# power.net
KiCad netlist of a schematic drawn in Altium Designer
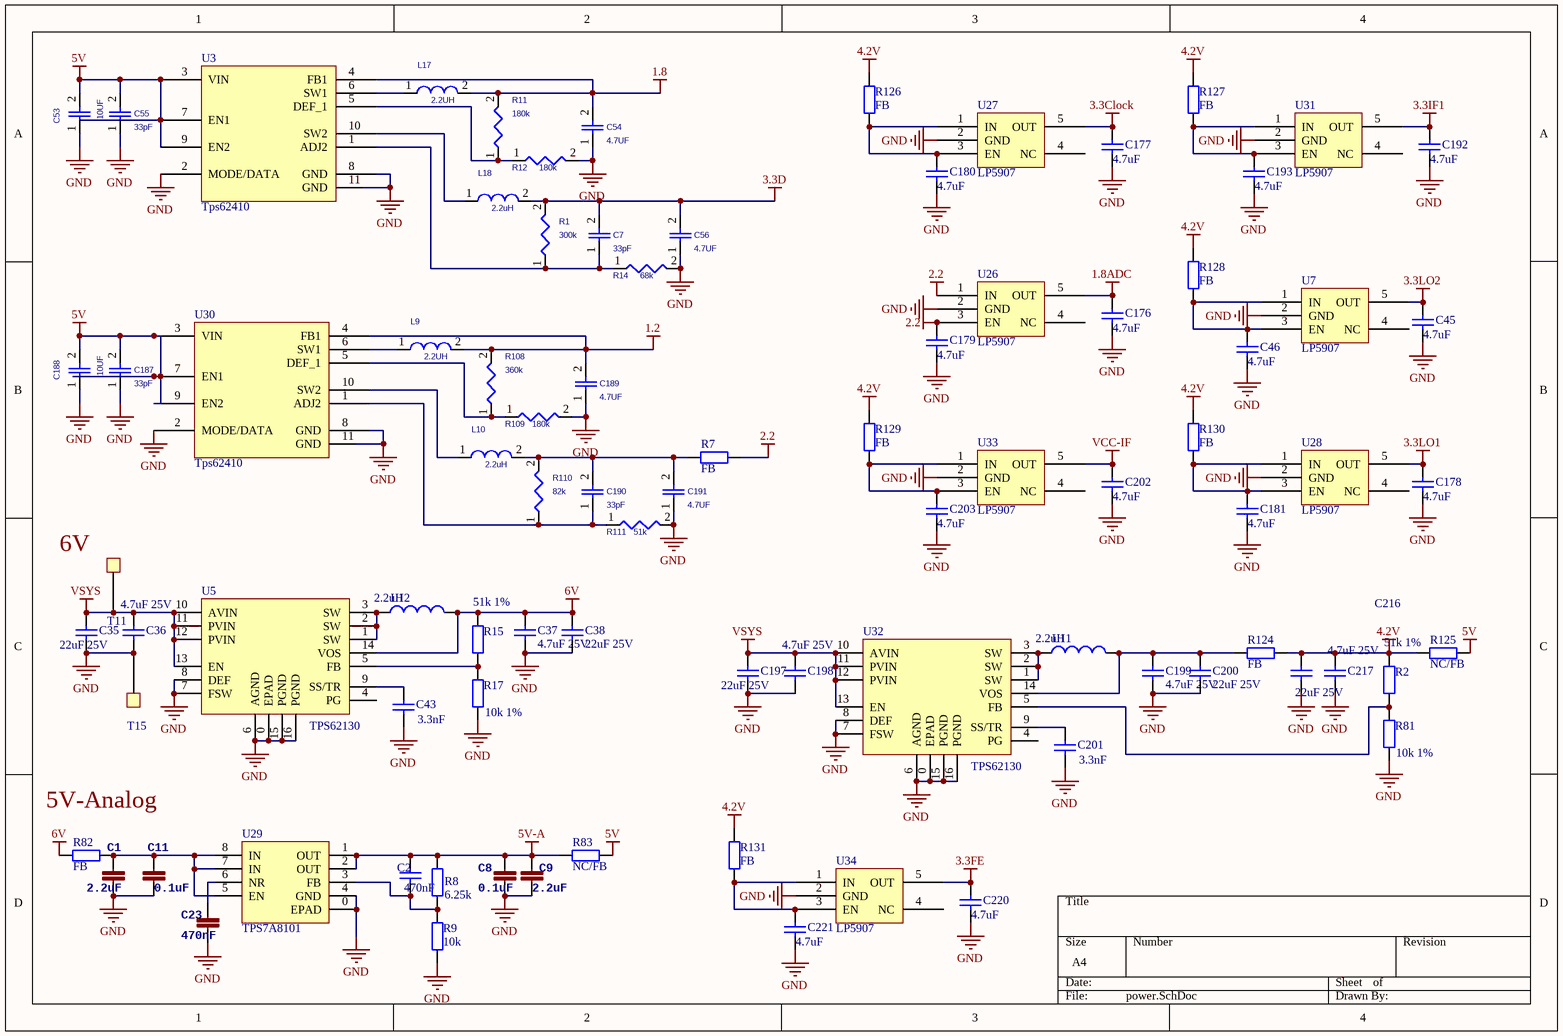
[diagram p0: power.SchDoc]

(export (version "E")
  (design (tool "Eeschema 10.0.6"))
  (components
    (comp (ref "C1")
      (value "2.2uF")
      (footprint "0603")
      (description "<b>Capacitor</b>\nStandard 0603 ceramic capacitor, and 0.1\" leaded capacitor.")
      (fields (field (name "PARTNO") "CC0402ZRY5V7BB104"))
      (libsource (lib "pixhawk2") (part "CAP0402-CAP"))
    )
    (comp (ref "C2")
      (value "470nF")
      (footprint "0402")
      (description "Capacitor")
      (fields (field (name "PUBLISHER") "Altium Limited"))
      (libsource (lib "RTC6705") (part "Cap"))
    )
    (comp (ref "C7") (value "33pF") (footprint "0402") (libsource (lib "*") (part "CAP/0402")))
    (comp (ref "C8")
      (value "0.1uF")
      (footprint "0603")
      (description "<b>Capacitor</b>\nStandard 0603 ceramic capacitor, and 0.1\" leaded capacitor.")
      (fields (field (name "PARTNO") "CC0402ZRY5V7BB104"))
      (libsource (lib "*") (part "CAP0402-CAP"))
    )
    (comp (ref "C9")
      (value "2.2uF")
      (footprint "0603")
      (description "<b>Capacitor</b>\nStandard 0603 ceramic capacitor, and 0.1\" leaded capacitor.")
      (fields (field (name "PARTNO") "CC0402ZRY5V7BB104"))
      (libsource (lib "pixhawk2") (part "CAP0402-CAP"))
    )
    (comp (ref "C11")
      (value "0.1uF")
      (footprint "0402")
      (description "<b>Capacitor</b>\nStandard 0603 ceramic capacitor, and 0.1\" leaded capacitor.")
      (fields (field (name "PARTNO") "CC0402ZRY5V7BB104"))
      (libsource (lib "*") (part "CAP0402-CAP"))
    )
    (comp (ref "C23")
      (value "470nF")
      (footprint "0402")
      (description "<b>Capacitor</b>\nStandard 0603 ceramic capacitor, and 0.1\" leaded capacitor.")
      (fields (field (name "PARTNO") "CC0402ZRY5V7BB104"))
      (libsource (lib "*") (part "CAP0402-CAP"))
    )
    (comp (ref "C35")
      (value "22uF 25V")
      (footprint "0805")
      (description "Capacitor")
      (fields (field (name "Comment") "Cap") (field (name "PUBLISHER") "Altium Limited"))
      (libsource (lib "RTC6705") (part "Cap"))
    )
    (comp (ref "C36")
      (value "4.7uF 25V")
      (footprint "0603")
      (description "Capacitor")
      (fields (field (name "Comment") "Cap") (field (name "PUBLISHER") "Altium Limited"))
      (libsource (lib "RTC6705") (part "Cap"))
    )
    (comp (ref "C37")
      (value "4.7uF 25V")
      (footprint "0603")
      (description "Capacitor")
      (fields (field (name "Comment") "Cap") (field (name "PUBLISHER") "Altium Limited"))
      (libsource (lib "RTC6705") (part "Cap"))
    )
    (comp (ref "C38")
      (value "22uF 25V")
      (footprint "0805")
      (description "Capacitor")
      (fields (field (name "Comment") "Cap") (field (name "PUBLISHER") "Altium Limited"))
      (libsource (lib "RTC6705") (part "Cap"))
    )
    (comp (ref "C43")
      (value "3.3nF")
      (footprint "0402")
      (description "Capacitor")
      (fields (field (name "PUBLISHER") "Altium Limited"))
      (libsource (lib "RTC6705") (part "Cap"))
    )
    (comp (ref "C45")
      (value "4.7uF")
      (footprint "0603")
      (description "Capacitor")
      (fields (field (name "PUBLISHER") "Altium Limited"))
      (libsource (lib "RTC6705") (part "Cap"))
    )
    (comp (ref "C46")
      (value "4.7uF")
      (footprint "0603")
      (description "Capacitor")
      (fields (field (name "PUBLISHER") "Altium Limited"))
      (libsource (lib "RTC6705") (part "Cap"))
    )
    (comp (ref "C53") (value "10UF") (footprint "0805") (libsource (lib "*") (part "CAP/0402")))
    (comp (ref "C54") (value "4.7UF") (footprint "0805") (libsource (lib "*") (part "CAP/0402")))
    (comp (ref "C55") (value "33pF") (footprint "0603") (libsource (lib "*") (part "CAP/0402")))
    (comp (ref "C56") (value "4.7UF") (footprint "0805") (libsource (lib "*") (part "CAP/0402")))
    (comp (ref "C176")
      (value "4.7uF")
      (footprint "0603")
      (description "Capacitor")
      (fields (field (name "PUBLISHER") "Altium Limited"))
      (libsource (lib "RTC6705") (part "Cap"))
    )
    (comp (ref "C177")
      (value "4.7uF")
      (footprint "0603")
      (description "Capacitor")
      (fields (field (name "PUBLISHER") "Altium Limited"))
      (libsource (lib "RTC6705") (part "Cap"))
    )
    (comp (ref "C178")
      (value "4.7uF")
      (footprint "0603")
      (description "Capacitor")
      (fields (field (name "PUBLISHER") "Altium Limited"))
      (libsource (lib "RTC6705") (part "Cap"))
    )
    (comp (ref "C179")
      (value "4.7uF")
      (footprint "0603")
      (description "Capacitor")
      (fields (field (name "PUBLISHER") "Altium Limited"))
      (libsource (lib "RTC6705") (part "Cap"))
    )
    (comp (ref "C180")
      (value "4.7uF")
      (footprint "0603")
      (description "Capacitor")
      (fields (field (name "PUBLISHER") "Altium Limited"))
      (libsource (lib "RTC6705") (part "Cap"))
    )
    (comp (ref "C181")
      (value "4.7uF")
      (footprint "0603")
      (description "Capacitor")
      (fields (field (name "PUBLISHER") "Altium Limited"))
      (libsource (lib "RTC6705") (part "Cap"))
    )
    (comp (ref "C187") (value "33pF") (footprint "0603") (libsource (lib "*") (part "CAP/0402")))
    (comp (ref "C188") (value "10UF") (footprint "0805") (libsource (lib "*") (part "CAP/0402")))
    (comp (ref "C189") (value "4.7UF") (footprint "0805") (libsource (lib "*") (part "CAP/0402")))
    (comp (ref "C190") (value "33pF") (footprint "0402") (libsource (lib "*") (part "CAP/0402")))
    (comp (ref "C191") (value "4.7UF") (footprint "0805") (libsource (lib "*") (part "CAP/0402")))
    (comp (ref "C192")
      (value "4.7uF")
      (footprint "0603")
      (description "Capacitor")
      (fields (field (name "PUBLISHER") "Altium Limited"))
      (libsource (lib "RTC6705") (part "Cap"))
    )
    (comp (ref "C193")
      (value "4.7uF")
      (footprint "0603")
      (description "Capacitor")
      (fields (field (name "PUBLISHER") "Altium Limited"))
      (libsource (lib "RTC6705") (part "Cap"))
    )
    (comp (ref "C197")
      (value "22uF 25V")
      (footprint "0805")
      (description "Capacitor")
      (fields (field (name "Comment") "Cap") (field (name "PUBLISHER") "Altium Limited"))
      (libsource (lib "RTC6705") (part "Cap"))
    )
    (comp (ref "C198")
      (value "4.7uF 25V")
      (footprint "0603")
      (description "Capacitor")
      (fields (field (name "Comment") "Cap") (field (name "PUBLISHER") "Altium Limited"))
      (libsource (lib "RTC6705") (part "Cap"))
    )
    (comp (ref "C199")
      (value "4.7uF 25V")
      (footprint "0603")
      (description "Capacitor")
      (fields (field (name "Comment") "Cap") (field (name "PUBLISHER") "Altium Limited"))
      (libsource (lib "RTC6705") (part "Cap"))
    )
    (comp (ref "C200")
      (value "22uF 25V")
      (footprint "0805")
      (description "Capacitor")
      (fields (field (name "Comment") "Cap") (field (name "PUBLISHER") "Altium Limited"))
      (libsource (lib "RTC6705") (part "Cap"))
    )
    (comp (ref "C201")
      (value "3.3nF")
      (footprint "0402")
      (description "Capacitor")
      (fields (field (name "PUBLISHER") "Altium Limited"))
      (libsource (lib "RTC6705") (part "Cap"))
    )
    (comp (ref "C202")
      (value "4.7uF")
      (footprint "0603")
      (description "Capacitor")
      (fields (field (name "PUBLISHER") "Altium Limited"))
      (libsource (lib "RTC6705") (part "Cap"))
    )
    (comp (ref "C203")
      (value "4.7uF")
      (footprint "0603")
      (description "Capacitor")
      (fields (field (name "PUBLISHER") "Altium Limited"))
      (libsource (lib "RTC6705") (part "Cap"))
    )
    (comp (ref "C216")
      (value "4.7uF 25V")
      (footprint "0603")
      (description "Capacitor")
      (fields (field (name "Comment") "Cap") (field (name "PUBLISHER") "Altium Limited"))
      (libsource (lib "RTC6705") (part "Cap"))
    )
    (comp (ref "C217")
      (value "22uF 25V")
      (footprint "0805")
      (description "Capacitor")
      (fields (field (name "Comment") "Cap") (field (name "PUBLISHER") "Altium Limited"))
      (libsource (lib "RTC6705") (part "Cap"))
    )
    (comp (ref "C220")
      (value "4.7uF")
      (footprint "0603")
      (description "Capacitor")
      (fields (field (name "PUBLISHER") "Altium Limited"))
      (libsource (lib "RTC6705") (part "Cap"))
    )
    (comp (ref "C221")
      (value "4.7uF")
      (footprint "0603")
      (description "Capacitor")
      (fields (field (name "PUBLISHER") "Altium Limited"))
      (libsource (lib "RTC6705") (part "Cap"))
    )
    (comp (ref "L9") (value "2.2UH") (footprint "0806") (libsource (lib "*") (part "L/2.5*2.0")))
    (comp (ref "L10") (value "2.2uH") (footprint "0806") (libsource (lib "*") (part "L/2.5*2.0")))
    (comp (ref "L11")
      (value "2.2uH")
      (footprint "L4015")
      (description "Inductor")
      (fields (field (name "PUBLISHER") "Altium Limited"))
      (libsource (lib "Miscellaneous Devices") (part "Inductor"))
    )
    (comp (ref "L12")
      (value "2.2uH")
      (footprint "L4015")
      (description "Inductor")
      (fields (field (name "PUBLISHER") "Altium Limited"))
      (libsource (lib "Miscellaneous Devices") (part "Inductor"))
    )
    (comp (ref "L17") (value "2.2UH") (footprint "0806") (libsource (lib "*") (part "L/2.5*2.0")))
    (comp (ref "L18") (value "2.2uH") (footprint "0806") (libsource (lib "*") (part "L/2.5*2.0")))
    (comp (ref "R1") (value "300k") (footprint "0402") (libsource (lib "*") (part "RES/0402_3")))
    (comp (ref "R2")
      (value "51k 1%")
      (footprint "0402")
      (description "Resistor")
      (fields (field (name "PUBLISHER") "Altium Limited"))
      (libsource (lib "RTC6705") (part "Res2"))
    )
    (comp (ref "R7")
      (value "FB")
      (footprint "0603")
      (description "Resistor")
      (fields (field (name "PUBLISHER") "Altium Limited"))
      (libsource (lib "") (part "Res2_1"))
    )
    (comp (ref "R8")
      (value "6.25k")
      (footprint "0402")
      (description "Resistor")
      (fields (field (name "PUBLISHER") "Altium Limited"))
      (libsource (lib "Miscellaneous Devices") (part "Res2"))
    )
    (comp (ref "R9")
      (value "10k")
      (footprint "0402")
      (description "Resistor")
      (fields (field (name "PUBLISHER") "Altium Limited"))
      (libsource (lib "Miscellaneous Devices") (part "Res2"))
    )
    (comp (ref "R11") (value "180k") (footprint "0402") (libsource (lib "*") (part "RES/0402_3")))
    (comp (ref "R12") (value "180k") (footprint "0402") (libsource (lib "*") (part "RES/0402_3")))
    (comp (ref "R14") (value "68k") (footprint "0402") (libsource (lib "*") (part "RES/0402_3")))
    (comp (ref "R15")
      (value "51k 1%")
      (footprint "0402")
      (description "Resistor")
      (fields (field (name "PUBLISHER") "Altium Limited"))
      (libsource (lib "RTC6705") (part "Res2"))
    )
    (comp (ref "R17")
      (value "10k 1%")
      (footprint "0402")
      (description "Resistor")
      (fields (field (name "PUBLISHER") "Altium Limited"))
      (libsource (lib "RTC6705") (part "Res2"))
    )
    (comp (ref "R81")
      (value "10k 1%")
      (footprint "0402")
      (description "Resistor")
      (fields (field (name "PUBLISHER") "Altium Limited"))
      (libsource (lib "RTC6705") (part "Res2"))
    )
    (comp (ref "R82")
      (value "FB")
      (footprint "0603")
      (description "Resistor")
      (fields (field (name "PUBLISHER") "Altium Limited"))
      (libsource (lib "") (part "Res2_1"))
    )
    (comp (ref "R83")
      (value "NC/FB")
      (footprint "0603")
      (description "Resistor")
      (fields (field (name "PUBLISHER") "Altium Limited"))
      (libsource (lib "") (part "Res2_1"))
    )
    (comp (ref "R108") (value "360k") (footprint "0402") (libsource (lib "*") (part "RES/0402_3")))
    (comp (ref "R109") (value "180k") (footprint "0402") (libsource (lib "*") (part "RES/0402_3")))
    (comp (ref "R110") (value "82k") (footprint "0402") (libsource (lib "*") (part "RES/0402_3")))
    (comp (ref "R111") (value "51k") (footprint "0402") (libsource (lib "*") (part "RES/0402_3")))
    (comp (ref "R124")
      (value "FB")
      (footprint "0603")
      (description "Resistor")
      (fields (field (name "PUBLISHER") "Altium Limited"))
      (libsource (lib "") (part "Res2_1"))
    )
    (comp (ref "R125")
      (value "NC/FB")
      (footprint "0603")
      (description "Resistor")
      (fields (field (name "PUBLISHER") "Altium Limited"))
      (libsource (lib "") (part "Res2_1"))
    )
    (comp (ref "R126")
      (value "FB")
      (footprint "0603")
      (description "Resistor")
      (fields (field (name "PUBLISHER") "Altium Limited"))
      (libsource (lib "Miscellaneous Devices") (part "Res2"))
    )
    (comp (ref "R127")
      (value "FB")
      (footprint "0603")
      (description "Resistor")
      (fields (field (name "PUBLISHER") "Altium Limited"))
      (libsource (lib "Miscellaneous Devices") (part "Res2"))
    )
    (comp (ref "R128")
      (value "FB")
      (footprint "0603")
      (description "Resistor")
      (fields (field (name "PUBLISHER") "Altium Limited"))
      (libsource (lib "Miscellaneous Devices") (part "Res2"))
    )
    (comp (ref "R129")
      (value "FB")
      (footprint "0603")
      (description "Resistor")
      (fields (field (name "PUBLISHER") "Altium Limited"))
      (libsource (lib "Miscellaneous Devices") (part "Res2"))
    )
    (comp (ref "R130")
      (value "FB")
      (footprint "0603")
      (description "Resistor")
      (fields (field (name "PUBLISHER") "Altium Limited"))
      (libsource (lib "Miscellaneous Devices") (part "Res2"))
    )
    (comp (ref "R131")
      (value "FB")
      (footprint "0603")
      (description "Resistor")
      (fields (field (name "PUBLISHER") "Altium Limited"))
      (libsource (lib "Miscellaneous Devices") (part "Res2"))
    )
    (comp (ref "T11") (value "TestPad") (footprint "TestPad") (libsource (lib "sch") (part "TestPad")))
    (comp (ref "T15") (value "TestPad") (footprint "TestPad") (libsource (lib "") (part "TestPad_1")))
    (comp (ref "U3") (value "Tps62410") (footprint "DFN-10P-3X3") (libsource (lib "Euler") (part "Tps62410")))
    (comp (ref "U5") (value "TPS62130") (footprint "TPS62130") (libsource (lib "sch") (part "TPS62130")))
    (comp (ref "U7") (value "LP5907") (footprint "SOT23-5") (libsource (lib "RTC6705") (part "LP5907")))
    (comp (ref "U26") (value "LP5907") (footprint "SOT23-5") (libsource (lib "RTC6705") (part "LP5907")))
    (comp (ref "U27") (value "LP5907") (footprint "SOT23-5") (libsource (lib "RTC6705") (part "LP5907")))
    (comp (ref "U28") (value "LP5907") (footprint "SOT23-5") (libsource (lib "RTC6705") (part "LP5907")))
    (comp (ref "U29")
      (value "TPS7A8101")
      (footprint "TPS7A8101")
      (libsource (lib "F4SDR") (part "TPS7A8101"))
    )
    (comp (ref "U30")
      (value "Tps62410")
      (footprint "DFN-10P-3X3")
      (libsource (lib "Euler") (part "Tps62410"))
    )
    (comp (ref "U31") (value "LP5907") (footprint "SOT23-5") (libsource (lib "RTC6705") (part "LP5907")))
    (comp (ref "U32") (value "TPS62130") (footprint "TPS62130") (libsource (lib "sch") (part "TPS62130")))
    (comp (ref "U33") (value "LP5907") (footprint "SOT23-5") (libsource (lib "RTC6705") (part "LP5907")))
    (comp (ref "U34") (value "LP5907") (footprint "SOT23-5") (libsource (lib "RTC6705") (part "LP5907")))
  )
  (nets
    (net (code "1") (name "1.2") (class "Default")
      (node (ref "C189") (pin "2") (pinfunction "2_2") (pintype "passive"))
      (node (ref "L9") (pin "2") (pinfunction "2_2") (pintype "passive"))
      (node (ref "R108") (pin "2") (pinfunction "2_2") (pintype "passive"))
      (node (ref "U30") (pin "4") (pinfunction "FB1_4") (pintype "passive"))
    )
    (net (code "2") (name "1.8") (class "Default")
      (node (ref "C54") (pin "2") (pinfunction "2_2") (pintype "passive"))
      (node (ref "L17") (pin "2") (pinfunction "2_2") (pintype "passive"))
      (node (ref "R11") (pin "2") (pinfunction "2_2") (pintype "passive"))
      (node (ref "U3") (pin "4") (pinfunction "FB1_4") (pintype "passive"))
    )
    (net (code "3") (name "1.8ADC") (class "Default")
      (node (ref "C176") (pin "2") (pinfunction "2_2") (pintype "passive"))
      (node (ref "U26") (pin "5") (pinfunction "OUT_5") (pintype "passive"))
    )
    (net (code "4") (name "2.2") (class "Default")
      (node (ref "C179") (pin "2") (pinfunction "2_2") (pintype "passive"))
      (node (ref "R7") (pin "1") (pinfunction "1_1") (pintype "passive"))
      (node (ref "U26") (pin "1") (pinfunction "IN_1") (pintype "passive"))
      (node (ref "U26") (pin "3") (pinfunction "EN_3") (pintype "passive"))
    )
    (net (code "5") (name "3.3Clock") (class "Default")
      (node (ref "C177") (pin "2") (pinfunction "2_2") (pintype "passive"))
      (node (ref "U27") (pin "5") (pinfunction "OUT_5") (pintype "passive"))
    )
    (net (code "6") (name "3.3D") (class "Default")
      (node (ref "C56") (pin "2") (pinfunction "2_2") (pintype "passive"))
      (node (ref "C7") (pin "2") (pinfunction "2_2") (pintype "passive"))
      (node (ref "L18") (pin "2") (pinfunction "2_2") (pintype "passive"))
      (node (ref "R1") (pin "2") (pinfunction "2_2") (pintype "passive"))
    )
    (net (code "7") (name "3.3FE") (class "Default")
      (node (ref "C220") (pin "2") (pinfunction "2_2") (pintype "passive"))
      (node (ref "U34") (pin "5") (pinfunction "OUT_5") (pintype "passive"))
    )
    (net (code "8") (name "3.3IF1") (class "Default")
      (node (ref "C192") (pin "2") (pinfunction "2_2") (pintype "passive"))
      (node (ref "U31") (pin "5") (pinfunction "OUT_5") (pintype "passive"))
    )
    (net (code "9") (name "3.3LO1") (class "Default")
      (node (ref "C178") (pin "2") (pinfunction "2_2") (pintype "passive"))
      (node (ref "U28") (pin "5") (pinfunction "OUT_5") (pintype "passive"))
    )
    (net (code "10") (name "3.3LO2") (class "Default")
      (node (ref "C45") (pin "2") (pinfunction "2_2") (pintype "passive"))
      (node (ref "U7") (pin "5") (pinfunction "OUT_5") (pintype "passive"))
    )
    (net (code "11") (name "4.2V") (class "Default")
      (node (ref "C216") (pin "2") (pinfunction "2_2") (pintype "passive"))
      (node (ref "C217") (pin "2") (pinfunction "2_2") (pintype "passive"))
      (node (ref "R124") (pin "1") (pinfunction "1_1") (pintype "passive"))
      (node (ref "R125") (pin "2") (pinfunction "2_2") (pintype "passive"))
      (node (ref "R126") (pin "1") (pinfunction "1_1") (pintype "passive"))
      (node (ref "R127") (pin "1") (pinfunction "1_1") (pintype "passive"))
      (node (ref "R128") (pin "1") (pinfunction "1_1") (pintype "passive"))
      (node (ref "R129") (pin "1") (pinfunction "1_1") (pintype "passive"))
      (node (ref "R130") (pin "1") (pinfunction "1_1") (pintype "passive"))
      (node (ref "R131") (pin "1") (pinfunction "1_1") (pintype "passive"))
      (node (ref "R2") (pin "1") (pinfunction "1_1") (pintype "passive"))
    )
    (net (code "12") (name "5V") (class "Default")
      (node (ref "C187") (pin "2") (pinfunction "2_2") (pintype "passive"))
      (node (ref "C188") (pin "2") (pinfunction "2_2") (pintype "passive"))
      (node (ref "C53") (pin "2") (pinfunction "2_2") (pintype "passive"))
      (node (ref "C55") (pin "2") (pinfunction "2_2") (pintype "passive"))
      (node (ref "R125") (pin "1") (pinfunction "1_1") (pintype "passive"))
      (node (ref "R83") (pin "1") (pinfunction "1_1") (pintype "passive"))
      (node (ref "U3") (pin "3") (pinfunction "VIN_3") (pintype "passive"))
      (node (ref "U3") (pin "7") (pinfunction "EN1_7") (pintype "passive"))
      (node (ref "U3") (pin "9") (pinfunction "EN2_9") (pintype "passive"))
      (node (ref "U30") (pin "3") (pinfunction "VIN_3") (pintype "passive"))
      (node (ref "U30") (pin "7") (pinfunction "EN1_7") (pintype "passive"))
      (node (ref "U30") (pin "9") (pinfunction "EN2_9") (pintype "passive"))
    )
    (net (code "13") (name "5V-A") (class "Default")
      (node (ref "C2") (pin "1") (pinfunction "1_1") (pintype "passive"))
      (node (ref "C8") (pin "2") (pinfunction "2_2") (pintype "passive"))
      (node (ref "C9") (pin "2") (pinfunction "2_2") (pintype "passive"))
      (node (ref "R8") (pin "1") (pinfunction "1_1") (pintype "passive"))
      (node (ref "R83") (pin "2") (pinfunction "2_2") (pintype "passive"))
      (node (ref "U29") (pin "1") (pinfunction "OUT_1") (pintype "passive"))
      (node (ref "U29") (pin "2") (pinfunction "OUT_2") (pintype "passive"))
    )
    (net (code "14") (name "6V") (class "Default")
      (node (ref "C37") (pin "2") (pinfunction "2_2") (pintype "passive"))
      (node (ref "C38") (pin "2") (pinfunction "2_2") (pintype "passive"))
      (node (ref "L12") (pin "2") (pinfunction "2_2") (pintype "passive"))
      (node (ref "R15") (pin "1") (pinfunction "1_1") (pintype "passive"))
      (node (ref "R82") (pin "2") (pinfunction "2_2") (pintype "passive"))
      (node (ref "U5") (pin "14") (pinfunction "VOS_14") (pintype "passive"))
    )
    (net (code "15") (name "GND") (class "Default")
      (node (ref "C1") (pin "1") (pinfunction "1_1") (pintype "passive"))
      (node (ref "C11") (pin "1") (pinfunction "1_1") (pintype "passive"))
      (node (ref "C176") (pin "1") (pinfunction "1_1") (pintype "passive"))
      (node (ref "C177") (pin "1") (pinfunction "1_1") (pintype "passive"))
      (node (ref "C178") (pin "1") (pinfunction "1_1") (pintype "passive"))
      (node (ref "C179") (pin "1") (pinfunction "1_1") (pintype "passive"))
      (node (ref "C180") (pin "1") (pinfunction "1_1") (pintype "passive"))
      (node (ref "C181") (pin "1") (pinfunction "1_1") (pintype "passive"))
      (node (ref "C187") (pin "1") (pinfunction "1_1") (pintype "passive"))
      (node (ref "C188") (pin "1") (pinfunction "1_1") (pintype "passive"))
      (node (ref "C189") (pin "1") (pinfunction "1_1") (pintype "passive"))
      (node (ref "C191") (pin "1") (pinfunction "1_1") (pintype "passive"))
      (node (ref "C192") (pin "1") (pinfunction "1_1") (pintype "passive"))
      (node (ref "C193") (pin "1") (pinfunction "1_1") (pintype "passive"))
      (node (ref "C197") (pin "2") (pinfunction "2_2") (pintype "passive"))
      (node (ref "C198") (pin "2") (pinfunction "2_2") (pintype "passive"))
      (node (ref "C199") (pin "1") (pinfunction "1_1") (pintype "passive"))
      (node (ref "C200") (pin "1") (pinfunction "1_1") (pintype "passive"))
      (node (ref "C201") (pin "2") (pinfunction "2_2") (pintype "passive"))
      (node (ref "C202") (pin "1") (pinfunction "1_1") (pintype "passive"))
      (node (ref "C203") (pin "1") (pinfunction "1_1") (pintype "passive"))
      (node (ref "C216") (pin "1") (pinfunction "1_1") (pintype "passive"))
      (node (ref "C217") (pin "1") (pinfunction "1_1") (pintype "passive"))
      (node (ref "C220") (pin "1") (pinfunction "1_1") (pintype "passive"))
      (node (ref "C221") (pin "1") (pinfunction "1_1") (pintype "passive"))
      (node (ref "C23") (pin "1") (pinfunction "1_1") (pintype "passive"))
      (node (ref "C35") (pin "2") (pinfunction "2_2") (pintype "passive"))
      (node (ref "C36") (pin "2") (pinfunction "2_2") (pintype "passive"))
      (node (ref "C37") (pin "1") (pinfunction "1_1") (pintype "passive"))
      (node (ref "C38") (pin "1") (pinfunction "1_1") (pintype "passive"))
      (node (ref "C43") (pin "2") (pinfunction "2_2") (pintype "passive"))
      (node (ref "C45") (pin "1") (pinfunction "1_1") (pintype "passive"))
      (node (ref "C46") (pin "1") (pinfunction "1_1") (pintype "passive"))
      (node (ref "C53") (pin "1") (pinfunction "1_1") (pintype "passive"))
      (node (ref "C54") (pin "1") (pinfunction "1_1") (pintype "passive"))
      (node (ref "C55") (pin "1") (pinfunction "1_1") (pintype "passive"))
      (node (ref "C56") (pin "1") (pinfunction "1_1") (pintype "passive"))
      (node (ref "C8") (pin "1") (pinfunction "1_1") (pintype "passive"))
      (node (ref "C9") (pin "1") (pinfunction "1_1") (pintype "passive"))
      (node (ref "R109") (pin "2") (pinfunction "2_2") (pintype "passive"))
      (node (ref "R111") (pin "2") (pinfunction "2_2") (pintype "passive"))
      (node (ref "R12") (pin "2") (pinfunction "2_2") (pintype "passive"))
      (node (ref "R14") (pin "2") (pinfunction "2_2") (pintype "passive"))
      (node (ref "R17") (pin "2") (pinfunction "2_2") (pintype "passive"))
      (node (ref "R81") (pin "2") (pinfunction "2_2") (pintype "passive"))
      (node (ref "R9") (pin "2") (pinfunction "2_2") (pintype "passive"))
      (node (ref "T15") (pin "1") (pinfunction "3_1") (pintype "passive"))
      (node (ref "U26") (pin "2") (pinfunction "GND_2") (pintype "passive"))
      (node (ref "U27") (pin "2") (pinfunction "GND_2") (pintype "passive"))
      (node (ref "U28") (pin "2") (pinfunction "GND_2") (pintype "passive"))
      (node (ref "U29") (pin "0") (pinfunction "EPAD_0") (pintype "passive"))
      (node (ref "U29") (pin "4") (pinfunction "GND_4") (pintype "passive"))
      (node (ref "U3") (pin "11") (pinfunction "GND_11") (pintype "passive"))
      (node (ref "U3") (pin "2") (pinfunction "MODE/DATA_2") (pintype "passive"))
      (node (ref "U3") (pin "8") (pinfunction "GND_8") (pintype "passive"))
      (node (ref "U30") (pin "11") (pinfunction "GND_11") (pintype "passive"))
      (node (ref "U30") (pin "2") (pinfunction "MODE/DATA_2") (pintype "passive"))
      (node (ref "U30") (pin "8") (pinfunction "GND_8") (pintype "passive"))
      (node (ref "U31") (pin "2") (pinfunction "GND_2") (pintype "passive"))
      (node (ref "U32") (pin "0") (pinfunction "EPAD_0") (pintype "passive"))
      (node (ref "U32") (pin "15") (pinfunction "PGND_15") (pintype "passive"))
      (node (ref "U32") (pin "16") (pinfunction "PGND_16") (pintype "passive"))
      (node (ref "U32") (pin "6") (pinfunction "AGND_6") (pintype "passive"))
      (node (ref "U32") (pin "7") (pinfunction "FSW_7") (pintype "passive"))
      (node (ref "U32") (pin "8") (pinfunction "DEF_8") (pintype "passive"))
      (node (ref "U33") (pin "2") (pinfunction "GND_2") (pintype "passive"))
      (node (ref "U34") (pin "2") (pinfunction "GND_2") (pintype "passive"))
      (node (ref "U5") (pin "0") (pinfunction "EPAD_0") (pintype "passive"))
      (node (ref "U5") (pin "15") (pinfunction "PGND_15") (pintype "passive"))
      (node (ref "U5") (pin "16") (pinfunction "PGND_16") (pintype "passive"))
      (node (ref "U5") (pin "6") (pinfunction "AGND_6") (pintype "passive"))
      (node (ref "U5") (pin "7") (pinfunction "FSW_7") (pintype "passive"))
      (node (ref "U5") (pin "8") (pinfunction "DEF_8") (pintype "passive"))
      (node (ref "U7") (pin "2") (pinfunction "GND_2") (pintype "passive"))
    )
    (net (code "16") (name "Net-(C190-Pad2)") (class "Default")
      (node (ref "C190") (pin "2") (pinfunction "2_2") (pintype "passive"))
      (node (ref "C191") (pin "2") (pinfunction "2_2") (pintype "passive"))
      (node (ref "L10") (pin "2") (pinfunction "2_2") (pintype "passive"))
      (node (ref "R110") (pin "2") (pinfunction "2_2") (pintype "passive"))
      (node (ref "R7") (pin "2") (pinfunction "2_2") (pintype "passive"))
    )
    (net (code "17") (name "Net-(L11-Pad1)") (class "Default")
      (node (ref "L11") (pin "1") (pinfunction "1_1") (pintype "passive"))
      (node (ref "U32") (pin "1") (pinfunction "SW_1") (pintype "passive"))
      (node (ref "U32") (pin "2") (pinfunction "SW_2") (pintype "passive"))
      (node (ref "U32") (pin "3") (pinfunction "SW_3") (pintype "passive"))
    )
    (net (code "18") (name "Net-(L12-Pad1)") (class "Default")
      (node (ref "L12") (pin "1") (pinfunction "1_1") (pintype "passive"))
      (node (ref "U5") (pin "1") (pinfunction "SW_1") (pintype "passive"))
      (node (ref "U5") (pin "2") (pinfunction "SW_2") (pintype "passive"))
      (node (ref "U5") (pin "3") (pinfunction "SW_3") (pintype "passive"))
    )
    (net (code "19") (name "Net-(U3-ADJ2)") (class "Default")
      (node (ref "C7") (pin "1") (pinfunction "1_1") (pintype "passive"))
      (node (ref "R1") (pin "1") (pinfunction "1_1") (pintype "passive"))
      (node (ref "R14") (pin "1") (pinfunction "1_1") (pintype "passive"))
      (node (ref "U3") (pin "1") (pinfunction "ADJ2_1") (pintype "passive"))
    )
    (net (code "20") (name "Net-(U3-DEF_1)") (class "Default")
      (node (ref "R11") (pin "1") (pinfunction "1_1") (pintype "passive"))
      (node (ref "R12") (pin "1") (pinfunction "1_1") (pintype "passive"))
      (node (ref "U3") (pin "5") (pinfunction "DEF_1_5") (pintype "passive"))
    )
    (net (code "21") (name "Net-(U3-SW1)") (class "Default")
      (node (ref "L17") (pin "1") (pinfunction "1_1") (pintype "passive"))
      (node (ref "U3") (pin "6") (pinfunction "SW1_6") (pintype "passive"))
    )
    (net (code "22") (name "Net-(U3-SW2)") (class "Default")
      (node (ref "L18") (pin "1") (pinfunction "1_1") (pintype "passive"))
      (node (ref "U3") (pin "10") (pinfunction "SW2_10") (pintype "passive"))
    )
    (net (code "23") (name "Net-(U5-FB)") (class "Default")
      (node (ref "R15") (pin "2") (pinfunction "2_2") (pintype "passive"))
      (node (ref "R17") (pin "1") (pinfunction "1_1") (pintype "passive"))
      (node (ref "U5") (pin "5") (pinfunction "FB_5") (pintype "passive"))
    )
    (net (code "24") (name "Net-(U5-SS{slash}TR)") (class "Default")
      (node (ref "C43") (pin "1") (pinfunction "1_1") (pintype "passive"))
      (node (ref "U5") (pin "9") (pinfunction "SS/TR_9") (pintype "passive"))
    )
    (net (code "25") (name "Net-(U7-EN)") (class "Default")
      (node (ref "C46") (pin "2") (pinfunction "2_2") (pintype "passive"))
      (node (ref "R128") (pin "2") (pinfunction "2_2") (pintype "passive"))
      (node (ref "U7") (pin "1") (pinfunction "IN_1") (pintype "passive"))
      (node (ref "U7") (pin "3") (pinfunction "EN_3") (pintype "passive"))
    )
    (net (code "26") (name "Net-(U27-EN)") (class "Default")
      (node (ref "C180") (pin "2") (pinfunction "2_2") (pintype "passive"))
      (node (ref "R126") (pin "2") (pinfunction "2_2") (pintype "passive"))
      (node (ref "U27") (pin "1") (pinfunction "IN_1") (pintype "passive"))
      (node (ref "U27") (pin "3") (pinfunction "EN_3") (pintype "passive"))
    )
    (net (code "27") (name "Net-(U28-EN)") (class "Default")
      (node (ref "C181") (pin "2") (pinfunction "2_2") (pintype "passive"))
      (node (ref "R130") (pin "2") (pinfunction "2_2") (pintype "passive"))
      (node (ref "U28") (pin "1") (pinfunction "IN_1") (pintype "passive"))
      (node (ref "U28") (pin "3") (pinfunction "EN_3") (pintype "passive"))
    )
    (net (code "28") (name "Net-(U29-EN)") (class "Default")
      (node (ref "C1") (pin "2") (pinfunction "2_2") (pintype "passive"))
      (node (ref "C11") (pin "2") (pinfunction "2_2") (pintype "passive"))
      (node (ref "R82") (pin "1") (pinfunction "1_1") (pintype "passive"))
      (node (ref "U29") (pin "5") (pinfunction "EN_5") (pintype "passive"))
      (node (ref "U29") (pin "7") (pinfunction "IN_7") (pintype "passive"))
      (node (ref "U29") (pin "8") (pinfunction "IN_8") (pintype "passive"))
    )
    (net (code "29") (name "Net-(U29-FB)") (class "Default")
      (node (ref "C2") (pin "2") (pinfunction "2_2") (pintype "passive"))
      (node (ref "R8") (pin "2") (pinfunction "2_2") (pintype "passive"))
      (node (ref "R9") (pin "1") (pinfunction "1_1") (pintype "passive"))
      (node (ref "U29") (pin "3") (pinfunction "FB_3") (pintype "passive"))
    )
    (net (code "30") (name "Net-(U29-NR)") (class "Default")
      (node (ref "C23") (pin "2") (pinfunction "2_2") (pintype "passive"))
      (node (ref "U29") (pin "6") (pinfunction "NR_6") (pintype "passive"))
    )
    (net (code "31") (name "Net-(U30-ADJ2)") (class "Default")
      (node (ref "C190") (pin "1") (pinfunction "1_1") (pintype "passive"))
      (node (ref "R110") (pin "1") (pinfunction "1_1") (pintype "passive"))
      (node (ref "R111") (pin "1") (pinfunction "1_1") (pintype "passive"))
      (node (ref "U30") (pin "1") (pinfunction "ADJ2_1") (pintype "passive"))
    )
    (net (code "32") (name "Net-(U30-DEF_1)") (class "Default")
      (node (ref "R108") (pin "1") (pinfunction "1_1") (pintype "passive"))
      (node (ref "R109") (pin "1") (pinfunction "1_1") (pintype "passive"))
      (node (ref "U30") (pin "5") (pinfunction "DEF_1_5") (pintype "passive"))
    )
    (net (code "33") (name "Net-(U30-SW1)") (class "Default")
      (node (ref "L9") (pin "1") (pinfunction "1_1") (pintype "passive"))
      (node (ref "U30") (pin "6") (pinfunction "SW1_6") (pintype "passive"))
    )
    (net (code "34") (name "Net-(U30-SW2)") (class "Default")
      (node (ref "L10") (pin "1") (pinfunction "1_1") (pintype "passive"))
      (node (ref "U30") (pin "10") (pinfunction "SW2_10") (pintype "passive"))
    )
    (net (code "35") (name "Net-(U31-EN)") (class "Default")
      (node (ref "C193") (pin "2") (pinfunction "2_2") (pintype "passive"))
      (node (ref "R127") (pin "2") (pinfunction "2_2") (pintype "passive"))
      (node (ref "U31") (pin "1") (pinfunction "IN_1") (pintype "passive"))
      (node (ref "U31") (pin "3") (pinfunction "EN_3") (pintype "passive"))
    )
    (net (code "36") (name "Net-(U32-FB)") (class "Default")
      (node (ref "R2") (pin "2") (pinfunction "2_2") (pintype "passive"))
      (node (ref "R81") (pin "1") (pinfunction "1_1") (pintype "passive"))
      (node (ref "U32") (pin "5") (pinfunction "FB_5") (pintype "passive"))
    )
    (net (code "37") (name "Net-(U32-SS{slash}TR)") (class "Default")
      (node (ref "C201") (pin "1") (pinfunction "1_1") (pintype "passive"))
      (node (ref "U32") (pin "9") (pinfunction "SS/TR_9") (pintype "passive"))
    )
    (net (code "38") (name "Net-(U32-VOS)") (class "Default")
      (node (ref "C199") (pin "2") (pinfunction "2_2") (pintype "passive"))
      (node (ref "C200") (pin "2") (pinfunction "2_2") (pintype "passive"))
      (node (ref "L11") (pin "2") (pinfunction "2_2") (pintype "passive"))
      (node (ref "R124") (pin "2") (pinfunction "2_2") (pintype "passive"))
      (node (ref "U32") (pin "14") (pinfunction "VOS_14") (pintype "passive"))
    )
    (net (code "39") (name "Net-(U33-EN)") (class "Default")
      (node (ref "C203") (pin "2") (pinfunction "2_2") (pintype "passive"))
      (node (ref "R129") (pin "2") (pinfunction "2_2") (pintype "passive"))
      (node (ref "U33") (pin "1") (pinfunction "IN_1") (pintype "passive"))
      (node (ref "U33") (pin "3") (pinfunction "EN_3") (pintype "passive"))
    )
    (net (code "40") (name "Net-(U34-EN)") (class "Default")
      (node (ref "C221") (pin "2") (pinfunction "2_2") (pintype "passive"))
      (node (ref "R131") (pin "2") (pinfunction "2_2") (pintype "passive"))
      (node (ref "U34") (pin "1") (pinfunction "IN_1") (pintype "passive"))
      (node (ref "U34") (pin "3") (pinfunction "EN_3") (pintype "passive"))
    )
    (net (code "41") (name "VCC-IF") (class "Default")
      (node (ref "C202") (pin "2") (pinfunction "2_2") (pintype "passive"))
      (node (ref "U33") (pin "5") (pinfunction "OUT_5") (pintype "passive"))
    )
    (net (code "42") (name "VSYS") (class "Default")
      (node (ref "C197") (pin "1") (pinfunction "1_1") (pintype "passive"))
      (node (ref "C198") (pin "1") (pinfunction "1_1") (pintype "passive"))
      (node (ref "C35") (pin "1") (pinfunction "1_1") (pintype "passive"))
      (node (ref "C36") (pin "1") (pinfunction "1_1") (pintype "passive"))
      (node (ref "T11") (pin "1") (pinfunction "3_1") (pintype "passive"))
      (node (ref "U32") (pin "10") (pinfunction "AVIN_10") (pintype "passive"))
      (node (ref "U32") (pin "11") (pinfunction "PVIN_11") (pintype "passive"))
      (node (ref "U32") (pin "12") (pinfunction "PVIN_12") (pintype "passive"))
      (node (ref "U32") (pin "13") (pinfunction "EN_13") (pintype "passive"))
      (node (ref "U5") (pin "10") (pinfunction "AVIN_10") (pintype "passive"))
      (node (ref "U5") (pin "11") (pinfunction "PVIN_11") (pintype "passive"))
      (node (ref "U5") (pin "12") (pinfunction "PVIN_12") (pintype "passive"))
      (node (ref "U5") (pin "13") (pinfunction "EN_13") (pintype "passive"))
    )
    (net (code "43") (name "unconnected-(U5-PG-Pad4)") (class "Default")
      (node (ref "U5") (pin "4") (pinfunction "PG_4") (pintype "passive"))
    )
    (net (code "44") (name "unconnected-(U7-NC-Pad4)") (class "Default")
      (node (ref "U7") (pin "4") (pinfunction "NC_4") (pintype "passive"))
    )
    (net (code "45") (name "unconnected-(U26-NC-Pad4)") (class "Default")
      (node (ref "U26") (pin "4") (pinfunction "NC_4") (pintype "passive"))
    )
    (net (code "46") (name "unconnected-(U27-NC-Pad4)") (class "Default")
      (node (ref "U27") (pin "4") (pinfunction "NC_4") (pintype "passive"))
    )
    (net (code "47") (name "unconnected-(U28-NC-Pad4)") (class "Default")
      (node (ref "U28") (pin "4") (pinfunction "NC_4") (pintype "passive"))
    )
    (net (code "48") (name "unconnected-(U31-NC-Pad4)") (class "Default")
      (node (ref "U31") (pin "4") (pinfunction "NC_4") (pintype "passive"))
    )
    (net (code "49") (name "unconnected-(U32-PG-Pad4)") (class "Default")
      (node (ref "U32") (pin "4") (pinfunction "PG_4") (pintype "passive"))
    )
    (net (code "50") (name "unconnected-(U33-NC-Pad4)") (class "Default")
      (node (ref "U33") (pin "4") (pinfunction "NC_4") (pintype "passive"))
    )
    (net (code "51") (name "unconnected-(U34-NC-Pad4)") (class "Default")
      (node (ref "U34") (pin "4") (pinfunction "NC_4") (pintype "passive"))
    )
  )
)
